# 1giri_3_k_paralel.net
KiCad netlist of a schematic drawn in EAGLE
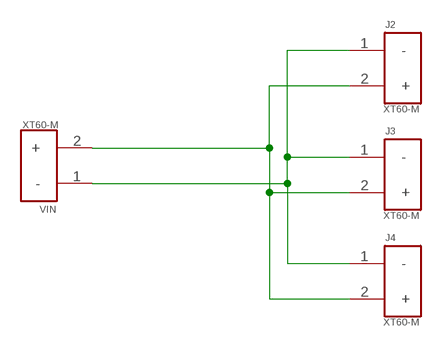
[diagram p0: schematic, sheet 1]

(export (version "E")
  (design (tool "Eeschema 10.0.6"))
  (components
    (comp (ref "J2")
      (value "XT60-M")
      (footprint "eagle-import:AMASS_XT60-M")
      (fields (field (name "MF") "AMASS"))
      (libsource (lib "eagle-import") (part "XT60-M"))
    )
    (comp (ref "J3")
      (value "XT60-M")
      (footprint "eagle-import:AMASS_XT60-M")
      (fields (field (name "MF") "AMASS"))
      (libsource (lib "eagle-import") (part "XT60-M"))
    )
    (comp (ref "J4")
      (value "XT60-M")
      (footprint "eagle-import:AMASS_XT60-M")
      (fields (field (name "MF") "AMASS"))
      (libsource (lib "eagle-import") (part "XT60-M"))
    )
    (comp (ref "VIN")
      (value "XT60-M")
      (footprint "eagle-import:AMASS_XT60-M")
      (fields (field (name "MF") "AMASS"))
      (libsource (lib "eagle-import") (part "XT60-M"))
    )
  )
  (nets
    (net (code "1") (name "Net-(J2-+)") (class "Default")
      (node (ref "J2") (pin "2") (pinfunction "+_2") (pintype "passive"))
      (node (ref "J3") (pin "2") (pinfunction "+_2") (pintype "passive"))
      (node (ref "J4") (pin "2") (pinfunction "+_2") (pintype "passive"))
      (node (ref "VIN") (pin "2") (pinfunction "+_2") (pintype "passive"))
    )
    (net (code "2") (name "Net-(J2--)") (class "Default")
      (node (ref "J2") (pin "1") (pinfunction "-_1") (pintype "passive"))
      (node (ref "J3") (pin "1") (pinfunction "-_1") (pintype "passive"))
      (node (ref "J4") (pin "1") (pinfunction "-_1") (pintype "passive"))
      (node (ref "VIN") (pin "1") (pinfunction "-_1") (pintype "passive"))
    )
  )
)
